# Circuit_Board_HM_1007_Interface.net
KiCad netlist of a schematic drawn in EAGLE
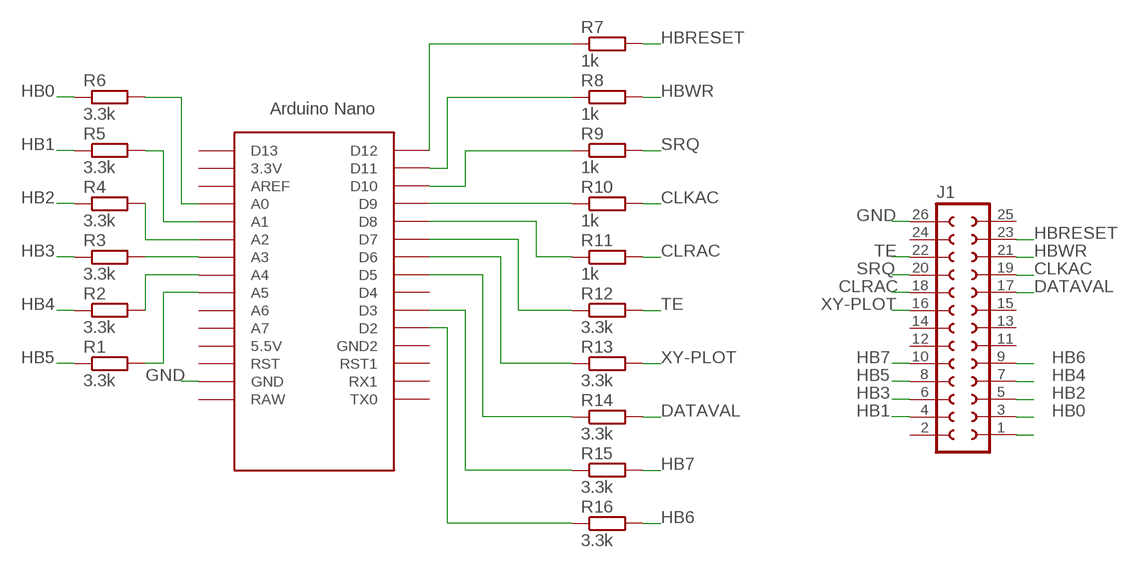
[diagram p0: schematic, sheet 1]

(export (version "E")
  (design (tool "Eeschema 10.0.6"))
  (components
    (comp (ref "J1")
      (value "SOCKET-26V")
      (footprint "eagle-import:S26V")
      (libsource (lib "eagle-import") (part "SOCKET-26V"))
    )
    (comp (ref "R1")
      (value "3.3k")
      (footprint "eagle-import:0204_7")
      (libsource (lib "eagle-import") (part "R-EU_0204/7"))
    )
    (comp (ref "R2")
      (value "3.3k")
      (footprint "eagle-import:0204_7")
      (libsource (lib "eagle-import") (part "R-EU_0204/7"))
    )
    (comp (ref "R3")
      (value "3.3k")
      (footprint "eagle-import:0204_7")
      (libsource (lib "eagle-import") (part "R-EU_0204/7"))
    )
    (comp (ref "R4")
      (value "3.3k")
      (footprint "eagle-import:0204_7")
      (libsource (lib "eagle-import") (part "R-EU_0204/7"))
    )
    (comp (ref "R5")
      (value "3.3k")
      (footprint "eagle-import:0204_7")
      (libsource (lib "eagle-import") (part "R-EU_0204/7"))
    )
    (comp (ref "R6")
      (value "3.3k")
      (footprint "eagle-import:0204_7")
      (libsource (lib "eagle-import") (part "R-EU_0204/7"))
    )
    (comp (ref "R7")
      (value "1k")
      (footprint "eagle-import:0204_7")
      (libsource (lib "eagle-import") (part "R-EU_0204/7"))
    )
    (comp (ref "R8")
      (value "1k")
      (footprint "eagle-import:0204_7")
      (libsource (lib "eagle-import") (part "R-EU_0204/7"))
    )
    (comp (ref "R9")
      (value "1k")
      (footprint "eagle-import:0204_7")
      (libsource (lib "eagle-import") (part "R-EU_0204/7"))
    )
    (comp (ref "R10")
      (value "1k")
      (footprint "eagle-import:0204_7")
      (libsource (lib "eagle-import") (part "R-EU_0204/7"))
    )
    (comp (ref "R11")
      (value "1k")
      (footprint "eagle-import:0204_7")
      (libsource (lib "eagle-import") (part "R-EU_0204/7"))
    )
    (comp (ref "R12")
      (value "3.3k")
      (footprint "eagle-import:0204_7")
      (libsource (lib "eagle-import") (part "R-EU_0204/7"))
    )
    (comp (ref "R13")
      (value "3.3k")
      (footprint "eagle-import:0204_7")
      (libsource (lib "eagle-import") (part "R-EU_0204/7"))
    )
    (comp (ref "R14")
      (value "3.3k")
      (footprint "eagle-import:0204_7")
      (libsource (lib "eagle-import") (part "R-EU_0204/7"))
    )
    (comp (ref "R15")
      (value "3.3k")
      (footprint "eagle-import:0204_7")
      (libsource (lib "eagle-import") (part "R-EU_0204/7"))
    )
    (comp (ref "R16")
      (value "3.3k")
      (footprint "eagle-import:0204_7")
      (libsource (lib "eagle-import") (part "R-EU_0204/7"))
    )
    (comp (ref "U$1")
      (value "NANO")
      (footprint "eagle-import:NANO")
      (libsource (lib "eagle-import") (part "NANO"))
    )
  )
  (nets
    (net (code "1") (name "/CLKAC") (class "Default")
      (node (ref "J1") (pin "19") (pinfunction "19_19") (pintype "passive"))
      (node (ref "R10") (pin "2") (pinfunction "2_2") (pintype "passive"))
    )
    (net (code "2") (name "/CLRAC") (class "Default")
      (node (ref "J1") (pin "18") (pinfunction "18_18") (pintype "passive"))
      (node (ref "R11") (pin "2") (pinfunction "2_2") (pintype "passive"))
    )
    (net (code "3") (name "/DATAVAL") (class "Default")
      (node (ref "J1") (pin "17") (pinfunction "17_17") (pintype "passive"))
      (node (ref "R14") (pin "2") (pinfunction "2_2") (pintype "passive"))
    )
    (net (code "4") (name "/GND") (class "Default")
      (node (ref "J1") (pin "26") (pinfunction "26_26") (pintype "passive"))
      (node (ref "U$1") (pin "GND") (pinfunction "GND_GND") (pintype "bidirectional"))
    )
    (net (code "5") (name "/HB0") (class "Default")
      (node (ref "J1") (pin "3") (pinfunction "3_3") (pintype "passive"))
      (node (ref "R6") (pin "1") (pinfunction "1_1") (pintype "passive"))
    )
    (net (code "6") (name "/HB1") (class "Default")
      (node (ref "J1") (pin "4") (pinfunction "4_4") (pintype "passive"))
      (node (ref "R5") (pin "1") (pinfunction "1_1") (pintype "passive"))
    )
    (net (code "7") (name "/HB2") (class "Default")
      (node (ref "J1") (pin "5") (pinfunction "5_5") (pintype "passive"))
      (node (ref "R4") (pin "1") (pinfunction "1_1") (pintype "passive"))
    )
    (net (code "8") (name "/HB3") (class "Default")
      (node (ref "J1") (pin "6") (pinfunction "6_6") (pintype "passive"))
      (node (ref "R3") (pin "1") (pinfunction "1_1") (pintype "passive"))
    )
    (net (code "9") (name "/HB4") (class "Default")
      (node (ref "J1") (pin "7") (pinfunction "7_7") (pintype "passive"))
      (node (ref "R2") (pin "1") (pinfunction "1_1") (pintype "passive"))
    )
    (net (code "10") (name "/HB5") (class "Default")
      (node (ref "J1") (pin "8") (pinfunction "8_8") (pintype "passive"))
      (node (ref "R1") (pin "1") (pinfunction "1_1") (pintype "passive"))
    )
    (net (code "11") (name "/HB6") (class "Default")
      (node (ref "J1") (pin "9") (pinfunction "9_9") (pintype "passive"))
      (node (ref "R16") (pin "2") (pinfunction "2_2") (pintype "passive"))
    )
    (net (code "12") (name "/HB7") (class "Default")
      (node (ref "J1") (pin "10") (pinfunction "10_10") (pintype "passive"))
      (node (ref "R15") (pin "2") (pinfunction "2_2") (pintype "passive"))
    )
    (net (code "13") (name "/HBRESET") (class "Default")
      (node (ref "J1") (pin "23") (pinfunction "23_23") (pintype "passive"))
      (node (ref "R7") (pin "2") (pinfunction "2_2") (pintype "passive"))
    )
    (net (code "14") (name "/HBWR") (class "Default")
      (node (ref "J1") (pin "21") (pinfunction "21_21") (pintype "passive"))
      (node (ref "R8") (pin "2") (pinfunction "2_2") (pintype "passive"))
    )
    (net (code "15") (name "/SRQ") (class "Default")
      (node (ref "J1") (pin "20") (pinfunction "20_20") (pintype "passive"))
      (node (ref "R9") (pin "2") (pinfunction "2_2") (pintype "passive"))
    )
    (net (code "16") (name "/TE") (class "Default")
      (node (ref "J1") (pin "22") (pinfunction "22_22") (pintype "passive"))
      (node (ref "R12") (pin "2") (pinfunction "2_2") (pintype "passive"))
    )
    (net (code "17") (name "/XY-PLOT") (class "Default")
      (node (ref "J1") (pin "16") (pinfunction "16_16") (pintype "passive"))
      (node (ref "R13") (pin "2") (pinfunction "2_2") (pintype "passive"))
    )
    (net (code "18") (name "Net-(R1-Pad2)") (class "Default")
      (node (ref "R1") (pin "2") (pinfunction "2_2") (pintype "passive"))
      (node (ref "U$1") (pin "A5") (pinfunction "A5_A5") (pintype "bidirectional"))
    )
    (net (code "19") (name "Net-(R2-Pad2)") (class "Default")
      (node (ref "R2") (pin "2") (pinfunction "2_2") (pintype "passive"))
      (node (ref "U$1") (pin "A4") (pinfunction "A4_A4") (pintype "bidirectional"))
    )
    (net (code "20") (name "Net-(R3-Pad2)") (class "Default")
      (node (ref "R3") (pin "2") (pinfunction "2_2") (pintype "passive"))
      (node (ref "U$1") (pin "A3") (pinfunction "A3_A3") (pintype "bidirectional"))
    )
    (net (code "21") (name "Net-(R4-Pad2)") (class "Default")
      (node (ref "R4") (pin "2") (pinfunction "2_2") (pintype "passive"))
      (node (ref "U$1") (pin "A2") (pinfunction "A2_A2") (pintype "bidirectional"))
    )
    (net (code "22") (name "Net-(R5-Pad2)") (class "Default")
      (node (ref "R5") (pin "2") (pinfunction "2_2") (pintype "passive"))
      (node (ref "U$1") (pin "A1") (pinfunction "A1_A1") (pintype "bidirectional"))
    )
    (net (code "23") (name "Net-(R6-Pad2)") (class "Default")
      (node (ref "R6") (pin "2") (pinfunction "2_2") (pintype "passive"))
      (node (ref "U$1") (pin "A0") (pinfunction "A0_A0") (pintype "bidirectional"))
    )
    (net (code "24") (name "Net-(R7-Pad1)") (class "Default")
      (node (ref "R7") (pin "1") (pinfunction "1_1") (pintype "passive"))
      (node (ref "U$1") (pin "D12") (pinfunction "D12_D12") (pintype "bidirectional"))
    )
    (net (code "25") (name "Net-(R8-Pad1)") (class "Default")
      (node (ref "R8") (pin "1") (pinfunction "1_1") (pintype "passive"))
      (node (ref "U$1") (pin "D11") (pinfunction "D11_D11") (pintype "bidirectional"))
    )
    (net (code "26") (name "Net-(R9-Pad1)") (class "Default")
      (node (ref "R9") (pin "1") (pinfunction "1_1") (pintype "passive"))
      (node (ref "U$1") (pin "D10") (pinfunction "D10_D10") (pintype "bidirectional"))
    )
    (net (code "27") (name "Net-(R10-Pad1)") (class "Default")
      (node (ref "R10") (pin "1") (pinfunction "1_1") (pintype "passive"))
      (node (ref "U$1") (pin "D9") (pinfunction "D9_D9") (pintype "bidirectional"))
    )
    (net (code "28") (name "Net-(R11-Pad1)") (class "Default")
      (node (ref "R11") (pin "1") (pinfunction "1_1") (pintype "passive"))
      (node (ref "U$1") (pin "D8") (pinfunction "D8_D8") (pintype "bidirectional"))
    )
    (net (code "29") (name "Net-(R12-Pad1)") (class "Default")
      (node (ref "R12") (pin "1") (pinfunction "1_1") (pintype "passive"))
      (node (ref "U$1") (pin "D7") (pinfunction "D7_D7") (pintype "bidirectional"))
    )
    (net (code "30") (name "Net-(R13-Pad1)") (class "Default")
      (node (ref "R13") (pin "1") (pinfunction "1_1") (pintype "passive"))
      (node (ref "U$1") (pin "D6") (pinfunction "D6_D6") (pintype "bidirectional"))
    )
    (net (code "31") (name "Net-(R14-Pad1)") (class "Default")
      (node (ref "R14") (pin "1") (pinfunction "1_1") (pintype "passive"))
      (node (ref "U$1") (pin "D5") (pinfunction "D5_D5") (pintype "bidirectional"))
    )
    (net (code "32") (name "Net-(R15-Pad1)") (class "Default")
      (node (ref "R15") (pin "1") (pinfunction "1_1") (pintype "passive"))
      (node (ref "U$1") (pin "D3") (pinfunction "D3_D3") (pintype "bidirectional"))
    )
    (net (code "33") (name "Net-(R16-Pad1)") (class "Default")
      (node (ref "R16") (pin "1") (pinfunction "1_1") (pintype "passive"))
      (node (ref "U$1") (pin "D2") (pinfunction "D2_D2") (pintype "bidirectional"))
    )
    (net (code "34") (name "unconnected-(J1-Pad1)") (class "Default")
      (node (ref "J1") (pin "1") (pinfunction "1_1") (pintype "passive"))
    )
    (net (code "35") (name "unconnected-(J1-Pad2)") (class "Default")
      (node (ref "J1") (pin "2") (pinfunction "2_2") (pintype "passive"))
    )
    (net (code "36") (name "unconnected-(J1-Pad11)") (class "Default")
      (node (ref "J1") (pin "11") (pinfunction "11_11") (pintype "passive"))
    )
    (net (code "37") (name "unconnected-(J1-Pad12)") (class "Default")
      (node (ref "J1") (pin "12") (pinfunction "12_12") (pintype "passive"))
    )
    (net (code "38") (name "unconnected-(J1-Pad13)") (class "Default")
      (node (ref "J1") (pin "13") (pinfunction "13_13") (pintype "passive"))
    )
    (net (code "39") (name "unconnected-(J1-Pad14)") (class "Default")
      (node (ref "J1") (pin "14") (pinfunction "14_14") (pintype "passive"))
    )
    (net (code "40") (name "unconnected-(J1-Pad15)") (class "Default")
      (node (ref "J1") (pin "15") (pinfunction "15_15") (pintype "passive"))
    )
    (net (code "41") (name "unconnected-(J1-Pad24)") (class "Default")
      (node (ref "J1") (pin "24") (pinfunction "24_24") (pintype "passive"))
    )
    (net (code "42") (name "unconnected-(J1-Pad25)") (class "Default")
      (node (ref "J1") (pin "25") (pinfunction "25_25") (pintype "passive"))
    )
    (net (code "43") (name "unconnected-(U$1-5.5V-Pad5V)") (class "Default")
      (node (ref "U$1") (pin "5V") (pinfunction "5.5V_5V") (pintype "bidirectional"))
    )
    (net (code "44") (name "unconnected-(U$1-GND2-PadGND1)") (class "Default")
      (node (ref "U$1") (pin "GND1") (pinfunction "GND2_GND1") (pintype "bidirectional"))
    )
    (net (code "45") (name "unconnected-(U$1-Pad3.3V)") (class "Default")
      (node (ref "U$1") (pin "3.3V") (pinfunction "3.3V_3.3V") (pintype "bidirectional"))
    )
    (net (code "46") (name "unconnected-(U$1-PadA6)") (class "Default")
      (node (ref "U$1") (pin "A6") (pinfunction "A6_A6") (pintype "bidirectional"))
    )
    (net (code "47") (name "unconnected-(U$1-PadA7)") (class "Default")
      (node (ref "U$1") (pin "A7") (pinfunction "A7_A7") (pintype "bidirectional"))
    )
    (net (code "48") (name "unconnected-(U$1-PadAREF)") (class "Default")
      (node (ref "U$1") (pin "AREF") (pinfunction "AREF_AREF") (pintype "bidirectional"))
    )
    (net (code "49") (name "unconnected-(U$1-PadD4)") (class "Default")
      (node (ref "U$1") (pin "D4") (pinfunction "D4_D4") (pintype "bidirectional"))
    )
    (net (code "50") (name "unconnected-(U$1-PadD13)") (class "Default")
      (node (ref "U$1") (pin "D13") (pinfunction "D13_D13") (pintype "bidirectional"))
    )
    (net (code "51") (name "unconnected-(U$1-PadICSP1)") (class "Default")
      (node (ref "U$1") (pin "ICSP1") (pinfunction "ICSP1_ICSP1") (pintype "bidirectional"))
    )
    (net (code "52") (name "unconnected-(U$1-PadICSP2)") (class "Default")
      (node (ref "U$1") (pin "ICSP2") (pinfunction "ICSP2_ICSP2") (pintype "bidirectional"))
    )
    (net (code "53") (name "unconnected-(U$1-PadICSP3)") (class "Default")
      (node (ref "U$1") (pin "ICSP3") (pinfunction "ICSP3_ICSP3") (pintype "bidirectional"))
    )
    (net (code "54") (name "unconnected-(U$1-PadICSP4)") (class "Default")
      (node (ref "U$1") (pin "ICSP4") (pinfunction "ICSP4_ICSP4") (pintype "bidirectional"))
    )
    (net (code "55") (name "unconnected-(U$1-PadICSP5)") (class "Default")
      (node (ref "U$1") (pin "ICSP5") (pinfunction "ICSP5_ICSP5") (pintype "bidirectional"))
    )
    (net (code "56") (name "unconnected-(U$1-PadICSP6)") (class "Default")
      (node (ref "U$1") (pin "ICSP6") (pinfunction "ICSP6_ICSP6") (pintype "bidirectional"))
    )
    (net (code "57") (name "unconnected-(U$1-PadRAW)") (class "Default")
      (node (ref "U$1") (pin "RAW") (pinfunction "RAW_RAW") (pintype "bidirectional"))
    )
    (net (code "58") (name "unconnected-(U$1-PadRST)") (class "Default")
      (node (ref "U$1") (pin "RST") (pinfunction "RST_RST") (pintype "bidirectional"))
    )
    (net (code "59") (name "unconnected-(U$1-PadRST1)") (class "Default")
      (node (ref "U$1") (pin "RST1") (pinfunction "RST1_RST1") (pintype "bidirectional"))
    )
    (net (code "60") (name "unconnected-(U$1-PadRX1)") (class "Default")
      (node (ref "U$1") (pin "RX1") (pinfunction "RX1_RX1") (pintype "bidirectional"))
    )
    (net (code "61") (name "unconnected-(U$1-PadTX0)") (class "Default")
      (node (ref "U$1") (pin "TX0") (pinfunction "TX0_TX0") (pintype "bidirectional"))
    )
  )
)
